# Mechanical.net
KiCad netlist of a schematic drawn in Altium Designer
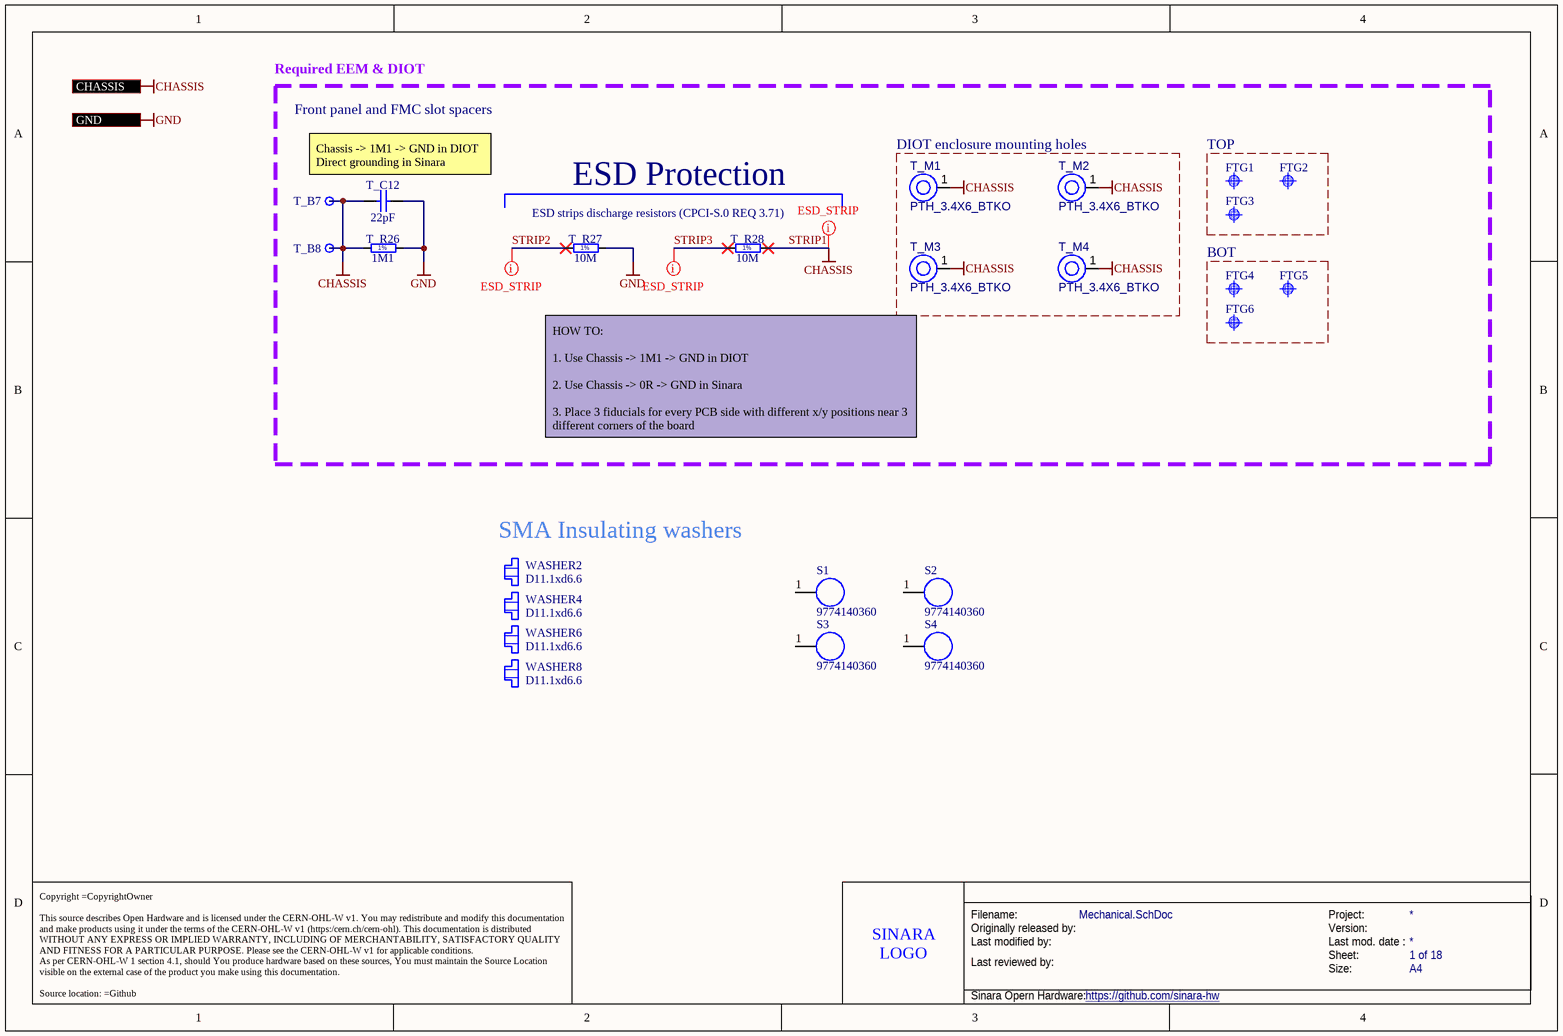
[diagram p0: Mechanical.SchDoc]

(export (version "E")
  (design (tool "Eeschema 10.0.6"))
  (components
    (comp (ref "FTG1")
      (value "Use only in PCB")
      (footprint "FIDUCIAL_TOP_C100-200")
      (description "Fiducial Target")
      (fields (field (name "PART NUMBER") "FIDUCIAL_TARGET_C100-200") (field (name "AUTHOR") "CERN DEM JLC"))
      (libsource (lib "Eletro-mechanical") (part "Fiducial Target"))
    )
    (comp (ref "FTG2")
      (value "Use only in PCB")
      (footprint "FIDUCIAL_TOP_S100-200")
      (description "Fiducial Target")
      (fields (field (name "PART NUMBER") "FIDUCIAL_TARGET_S100-200") (field (name "AUTHOR") "CERN DEM JLC"))
      (libsource (lib "Eletro-mechanical") (part "Fiducial Target"))
    )
    (comp (ref "FTG3")
      (value "Use only in PCB")
      (footprint "FIDUCIAL_TOP_S100-200")
      (description "Fiducial Target")
      (fields (field (name "PART NUMBER") "FIDUCIAL_TARGET_S100-200") (field (name "AUTHOR") "CERN DEM JLC"))
      (libsource (lib "Eletro-mechanical") (part "Fiducial Target"))
    )
    (comp (ref "FTG4")
      (value "Use only in PCB")
      (footprint "FIDUCIAL_TOP_C100-200")
      (description "Fiducial Target")
      (fields (field (name "PART NUMBER") "FIDUCIAL_TARGET_C100-200") (field (name "AUTHOR") "CERN DEM JLC"))
      (libsource (lib "Eletro-mechanical") (part "Fiducial Target"))
    )
    (comp (ref "FTG5")
      (value "Use only in PCB")
      (footprint "FIDUCIAL_TOP_S100-200")
      (description "Fiducial Target")
      (fields (field (name "PART NUMBER") "FIDUCIAL_TARGET_S100-200") (field (name "AUTHOR") "CERN DEM JLC"))
      (libsource (lib "Eletro-mechanical") (part "Fiducial Target"))
    )
    (comp (ref "FTG6")
      (value "Use only in PCB")
      (footprint "FIDUCIAL_TOP_S100-200")
      (description "Fiducial Target")
      (fields (field (name "PART NUMBER") "FIDUCIAL_TARGET_S100-200") (field (name "AUTHOR") "CERN DEM JLC"))
      (libsource (lib "Eletro-mechanical") (part "Fiducial Target"))
    )
    (comp (ref "S1")
      (value "9774140360")
      (footprint "9774140360")
      (description "WA-SMSI SMD Steel Spacer with internal Thread")
      (fields (field (name "MANUFACTURER") "Wurth Elektronik") (field (name "CREATED BY") "Baojun Chen"))
      (libsource (lib "Altium_SMSI_SMT_STEEL_SPACER_M2_5_THREAD_INTERNAL_rev15a") (part "WA-SMSI,  9774140360"))
    )
    (comp (ref "S2")
      (value "9774140360")
      (footprint "9774140360")
      (description "WA-SMSI SMD Steel Spacer with internal Thread")
      (fields (field (name "MANUFACTURER") "Wurth Elektronik") (field (name "CREATED BY") "Baojun Chen"))
      (libsource (lib "Altium_SMSI_SMT_STEEL_SPACER_M2_5_THREAD_INTERNAL_rev15a") (part "WA-SMSI,  9774140360"))
    )
    (comp (ref "S3")
      (value "9774140360")
      (footprint "9774140360")
      (description "WA-SMSI SMD Steel Spacer with internal Thread")
      (fields (field (name "MANUFACTURER") "Wurth Elektronik") (field (name "CREATED BY") "Baojun Chen"))
      (libsource (lib "Altium_SMSI_SMT_STEEL_SPACER_M2_5_THREAD_INTERNAL_rev15a") (part "WA-SMSI,  9774140360"))
    )
    (comp (ref "S4")
      (value "9774140360")
      (footprint "9774140360")
      (description "WA-SMSI SMD Steel Spacer with internal Thread")
      (fields (field (name "MANUFACTURER") "Wurth Elektronik") (field (name "CREATED BY") "Baojun Chen"))
      (libsource (lib "Altium_SMSI_SMT_STEEL_SPACER_M2_5_THREAD_INTERNAL_rev15a") (part "WA-SMSI,  9774140360"))
    )
    (comp (ref "T_B7")
      (value "Plated Hole")
      (footprint "c600h270")
      (description "Single Terminal Socket")
      (fields (field (name "PART NUMBER") "PLATED_HOLE2.7_PAD6.0") (field (name "AUTHOR") "CERN DEM HF"))
      (libsource (lib "Eletro-mechanical") (part "Single Terminal Socket"))
    )
    (comp (ref "T_B8")
      (value "Plated Hole")
      (footprint "c600h270")
      (description "Single Terminal Socket")
      (fields (field (name "PART NUMBER") "PLATED_HOLE2.7_PAD6.0") (field (name "AUTHOR") "CERN DEM HF"))
      (libsource (lib "Eletro-mechanical") (part "Single Terminal Socket"))
    )
    (comp (ref "T_C12")
      (value "22pF")
      (footprint "CAPC1005X55N")
      (description "Non-polarised capacitor")
      (fields
        (field (name "PART NUMBER") "CC0402_22PF_50V_5%_C0G")
        (field (name "VOLTAGE") "50V")
        (field (name "AUTHOR") "CERN DEM JLC")
      )
      (libsource (lib "Capacitors") (part "Capacitor - non polarized"))
    )
    (comp (ref "T_M1")
      (value "PTH_3.4X6_BTKO")
      (footprint "PTH-M3.4x6.0_BTKO")
      (description "PTH  Hole 3.4, 6mm pad")
      (libsource (lib "TechnoSystem Workspace") (part "PTH3.4x6.0_BTKO"))
    )
    (comp (ref "T_M2")
      (value "PTH_3.4X6_BTKO")
      (footprint "PTH-M3.4x6.0_BTKO")
      (description "PTH  Hole 3.4, 6mm pad")
      (libsource (lib "TechnoSystem Workspace") (part "PTH3.4x6.0_BTKO"))
    )
    (comp (ref "T_M3")
      (value "PTH_3.4X6_BTKO")
      (footprint "PTH-M3.4x6.0_BTKO")
      (description "PTH  Hole 3.4, 6mm pad")
      (libsource (lib "TechnoSystem Workspace") (part "PTH3.4x6.0_BTKO"))
    )
    (comp (ref "T_M4")
      (value "PTH_3.4X6_BTKO")
      (footprint "PTH-M3.4x6.0_BTKO")
      (description "PTH  Hole 3.4, 6mm pad")
      (libsource (lib "TechnoSystem Workspace") (part "PTH3.4x6.0_BTKO"))
    )
    (comp (ref "T_R26")
      (value "1M1")
      (footprint "RESC2012X60N")
      (description "Resistor - 1%")
      (fields
        (field (name "PART NUMBER") "R0805_1M1_1%_0.125W_100PPM")
        (field (name "MANUFACTURER") "GENERIC")
        (field (name "AUTHOR") "CERN DEM JLC")
      )
      (libsource (lib "Resistors") (part "Resistor - 1%"))
    )
    (comp (ref "T_R27")
      (value "10M")
      (footprint "RESC2113X55N")
      (description "Resistor - 1%")
      (fields
        (field (name "PART NUMBER") "R0805_10M_1%_0.125W_100PPM_VISHAY_CRCW e3")
        (field (name "POWER") "0.125W")
        (field (name "AUTHOR") "CERN DEM BC")
      )
      (libsource (lib "Resistors") (part "Resistor - 1%"))
    )
    (comp (ref "T_R28")
      (value "10M")
      (footprint "RESC2113X55N")
      (description "Resistor - 1%")
      (fields
        (field (name "PART NUMBER") "R0805_10M_1%_0.125W_100PPM_VISHAY_CRCW e3")
        (field (name "POWER") "0.125W")
        (field (name "AUTHOR") "CERN DEM BC")
      )
      (libsource (lib "Resistors") (part "Resistor - 1%"))
    )
    (comp (ref "WASHER2")
      (value "D11.1xd6.6")
      (footprint "Keystone_7687")
      (description "SMA_Shoulder Washer")
      (fields (field (name "PART NUMBER") "custom 3D") (field (name "AUTHOR") "GK"))
      (libsource (lib "LIBRARY_SCH") (part "Keystone_7687"))
    )
    (comp (ref "WASHER4")
      (value "D11.1xd6.6")
      (footprint "Keystone_7687")
      (description "SMA_Shoulder Washer")
      (fields (field (name "PART NUMBER") "custom 3D") (field (name "AUTHOR") "GK"))
      (libsource (lib "LIBRARY_SCH") (part "Keystone_7687"))
    )
    (comp (ref "WASHER6")
      (value "D11.1xd6.6")
      (footprint "Keystone_7687")
      (description "SMA_Shoulder Washer")
      (fields (field (name "PART NUMBER") "custom 3D") (field (name "AUTHOR") "GK"))
      (libsource (lib "LIBRARY_SCH") (part "Keystone_7687"))
    )
    (comp (ref "WASHER8")
      (value "D11.1xd6.6")
      (footprint "Keystone_7687")
      (description "SMA_Shoulder Washer")
      (fields (field (name "PART NUMBER") "custom 3D") (field (name "AUTHOR") "GK"))
      (libsource (lib "LIBRARY_SCH") (part "Keystone_7687"))
    )
  )
  (nets
    (net (code "1") (name "/STRIP2") (class "Default")
      (node (ref "T_R27") (pin "1") (pinfunction "1_1") (pintype "passive+no_connect"))
    )
    (net (code "2") (name "/STRIP3") (class "Default")
      (node (ref "T_R28") (pin "1") (pinfunction "1_1") (pintype "passive+no_connect"))
    )
    (net (code "3") (name "CHASSIS") (class "Default")
      (node (ref "T_B7") (pin "1") (pinfunction "1_1") (pintype "bidirectional"))
      (node (ref "T_B8") (pin "1") (pinfunction "1_1") (pintype "bidirectional"))
      (node (ref "T_C12") (pin "1") (pinfunction "1_1") (pintype "passive"))
      (node (ref "T_M1") (pin "1") (pinfunction "H1_1") (pintype "passive"))
      (node (ref "T_M2") (pin "1") (pinfunction "H1_1") (pintype "passive"))
      (node (ref "T_M3") (pin "1") (pinfunction "H1_1") (pintype "passive"))
      (node (ref "T_M4") (pin "1") (pinfunction "H1_1") (pintype "passive"))
      (node (ref "T_R26") (pin "1") (pinfunction "1_1") (pintype "passive"))
      (node (ref "T_R28") (pin "2") (pinfunction "2_2") (pintype "passive"))
    )
    (net (code "4") (name "GND") (class "Default")
      (node (ref "T_C12") (pin "2") (pinfunction "2_2") (pintype "passive"))
      (node (ref "T_R26") (pin "2") (pinfunction "2_2") (pintype "passive"))
      (node (ref "T_R27") (pin "2") (pinfunction "2_2") (pintype "passive"))
    )
    (net (code "5") (name "unconnected-(S1-Pad1)") (class "Default")
      (node (ref "S1") (pin "1") (pinfunction "1_1") (pintype "passive"))
    )
    (net (code "6") (name "unconnected-(S2-Pad1)") (class "Default")
      (node (ref "S2") (pin "1") (pinfunction "1_1") (pintype "passive"))
    )
    (net (code "7") (name "unconnected-(S3-Pad1)") (class "Default")
      (node (ref "S3") (pin "1") (pinfunction "1_1") (pintype "passive"))
    )
    (net (code "8") (name "unconnected-(S4-Pad1)") (class "Default")
      (node (ref "S4") (pin "1") (pinfunction "1_1") (pintype "passive"))
    )
  )
)
